# untitled.net
KiCad netlist of a schematic drawn in EAGLE
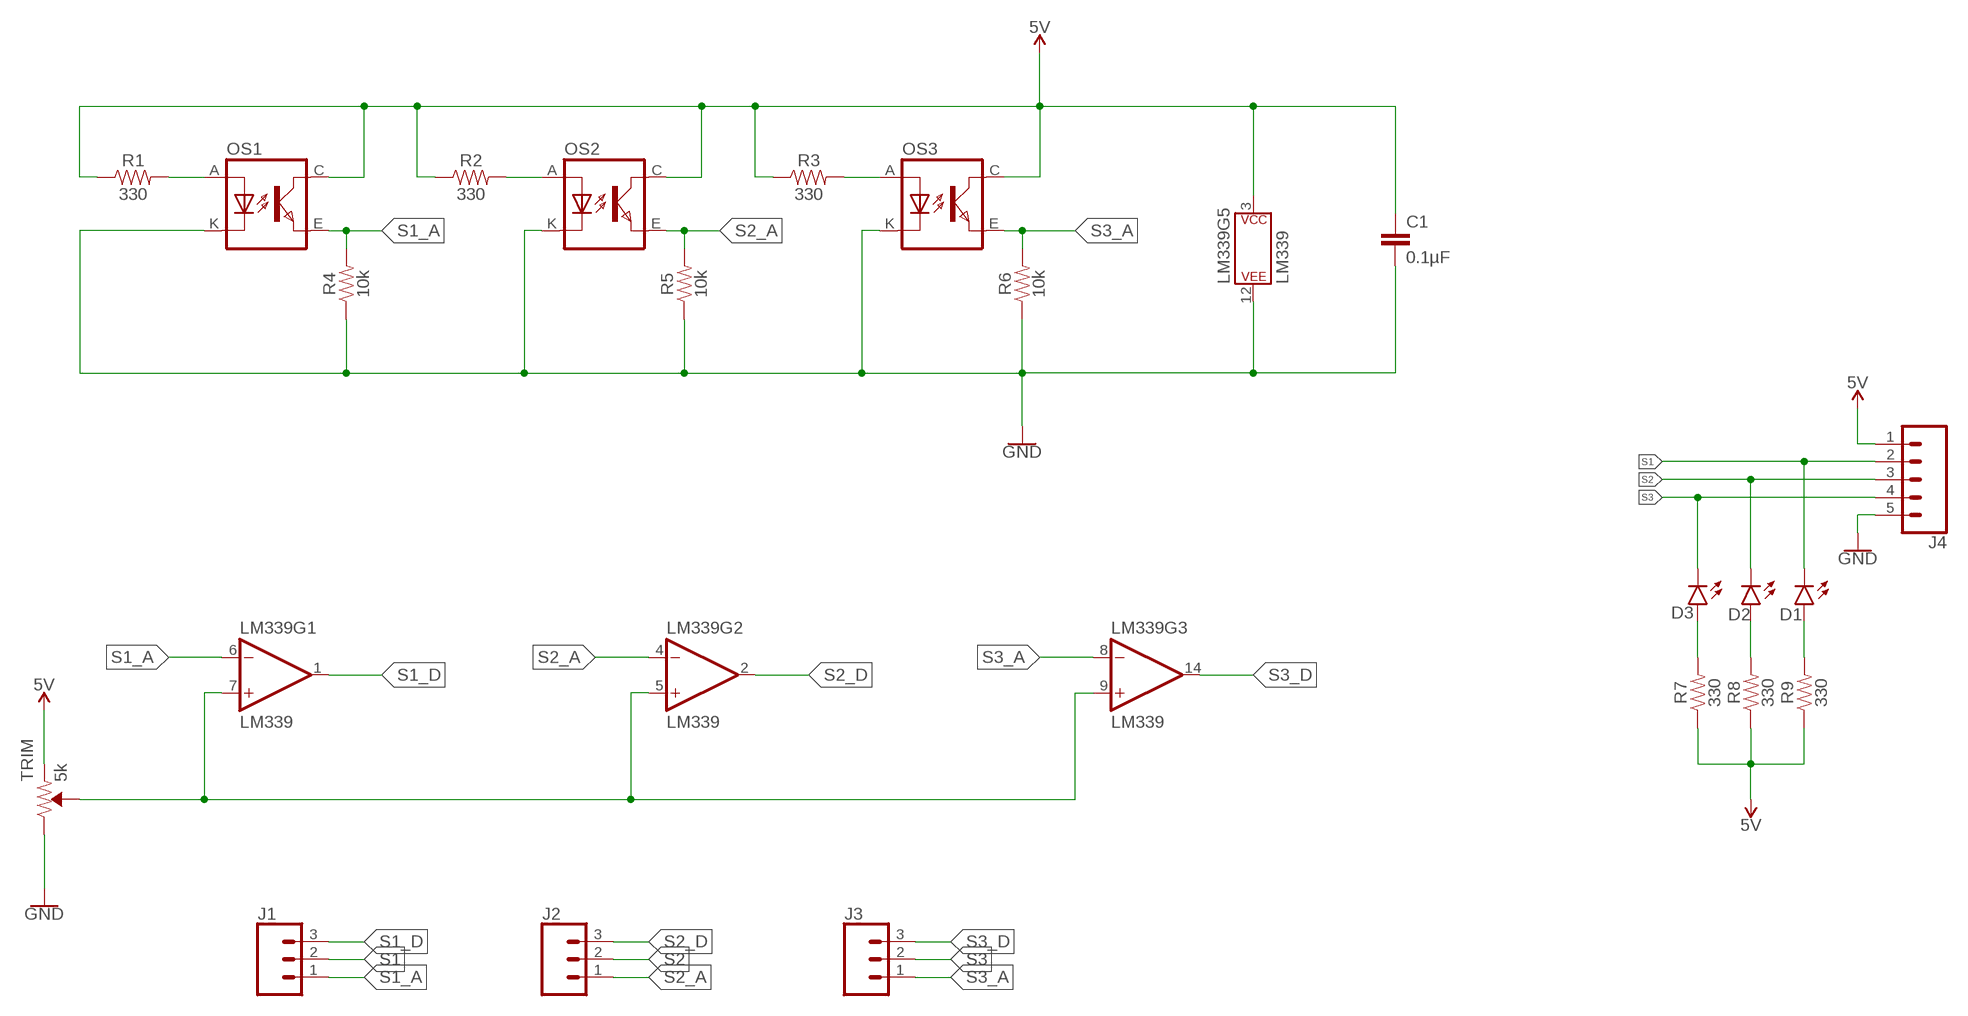
[diagram p0: schematic, sheet 1]

(export (version "E")
  (design (tool "Eeschema 10.0.6"))
  (components
    (comp (ref "C1")
      (value "0.1µF")
      (footprint "eagle-import:0805")
      (libsource (lib "eagle-import") (part "0.33UF/330NF-0805-50V-10%"))
    )
    (comp (ref "D1")
      (value "LED-RED-0805")
      (footprint "eagle-import:LED-0805")
      (libsource (lib "eagle-import") (part "LED-RED-0805"))
    )
    (comp (ref "D2")
      (value "LED-RED-0805")
      (footprint "eagle-import:LED-0805")
      (libsource (lib "eagle-import") (part "LED-RED-0805"))
    )
    (comp (ref "D3")
      (value "LED-RED-0805")
      (footprint "eagle-import:LED-0805")
      (libsource (lib "eagle-import") (part "LED-RED-0805"))
    )
    (comp (ref "J1")
      (value "CONN_03")
      (footprint "eagle-import:1X03")
      (libsource (lib "eagle-import") (part "CONN_03"))
    )
    (comp (ref "J2")
      (value "CONN_03")
      (footprint "eagle-import:1X03")
      (libsource (lib "eagle-import") (part "CONN_03"))
    )
    (comp (ref "J3")
      (value "CONN_03")
      (footprint "eagle-import:1X03")
      (libsource (lib "eagle-import") (part "CONN_03"))
    )
    (comp (ref "J4")
      (value "CONN_05PTH")
      (footprint "eagle-import:1X05")
      (libsource (lib "eagle-import") (part "CONN_05PTH"))
    )
    (comp (ref "LM339")
      (value "LM339")
      (footprint "eagle-import:TSSOP-14")
      (libsource (lib "eagle-import") (part "LM339"))
    )
    (comp (ref "OS1")
      (value "TCRT5000")
      (footprint "eagle-import:TCRT5000")
      (libsource (lib "eagle-import") (part "TCRT5000"))
    )
    (comp (ref "OS2")
      (value "TCRT5000")
      (footprint "eagle-import:TCRT5000")
      (libsource (lib "eagle-import") (part "TCRT5000"))
    )
    (comp (ref "OS3")
      (value "TCRT5000")
      (footprint "eagle-import:TCRT5000")
      (libsource (lib "eagle-import") (part "TCRT5000"))
    )
    (comp (ref "R1")
      (value "330")
      (footprint "eagle-import:0805")
      (libsource (lib "eagle-import") (part "0.3OHM-0805-1/8W-1%"))
    )
    (comp (ref "R2")
      (value "330")
      (footprint "eagle-import:0805")
      (libsource (lib "eagle-import") (part "0.3OHM-0805-1/8W-1%"))
    )
    (comp (ref "R3")
      (value "330")
      (footprint "eagle-import:0805")
      (libsource (lib "eagle-import") (part "0.3OHM-0805-1/8W-1%"))
    )
    (comp (ref "R4")
      (value "10k")
      (footprint "eagle-import:0805")
      (libsource (lib "eagle-import") (part "0.3OHM-0805-1/8W-1%"))
    )
    (comp (ref "R5")
      (value "10k")
      (footprint "eagle-import:0805")
      (libsource (lib "eagle-import") (part "0.3OHM-0805-1/8W-1%"))
    )
    (comp (ref "R6")
      (value "10k")
      (footprint "eagle-import:0805")
      (libsource (lib "eagle-import") (part "0.3OHM-0805-1/8W-1%"))
    )
    (comp (ref "R7")
      (value "330")
      (footprint "eagle-import:0805")
      (libsource (lib "eagle-import") (part "0.3OHM-0805-1/8W-1%"))
    )
    (comp (ref "R8")
      (value "330")
      (footprint "eagle-import:0805")
      (libsource (lib "eagle-import") (part "0.3OHM-0805-1/8W-1%"))
    )
    (comp (ref "R9")
      (value "330")
      (footprint "eagle-import:0805")
      (libsource (lib "eagle-import") (part "0.3OHM-0805-1/8W-1%"))
    )
    (comp (ref "TRIM")
      (value "5k")
      (footprint "eagle-import:TRIMPOT-SMD-5MM")
      (libsource (lib "eagle-import") (part "TRIMPOT-SMD-5MM-CLOSED-1/4W-20%"))
    )
  )
  (nets
    (net (code "1") (name "5V") (class "Default")
      (node (ref "C1") (pin "1") (pinfunction "1_1") (pintype "passive"))
      (node (ref "J4") (pin "1") (pinfunction "1_1") (pintype "passive"))
      (node (ref "LM339") (pin "3") (pinfunction "P$V+_3") (pintype "bidirectional"))
      (node (ref "OS1") (pin "C") (pinfunction "COLLECTOR_C") (pintype "passive"))
      (node (ref "OS2") (pin "C") (pinfunction "COLLECTOR_C") (pintype "passive"))
      (node (ref "OS3") (pin "C") (pinfunction "COLLECTOR_C") (pintype "passive"))
      (node (ref "R1") (pin "1") (pinfunction "1_1") (pintype "passive"))
      (node (ref "R2") (pin "1") (pinfunction "1_1") (pintype "passive"))
      (node (ref "R3") (pin "1") (pinfunction "1_1") (pintype "passive"))
      (node (ref "R7") (pin "1") (pinfunction "1_1") (pintype "passive"))
      (node (ref "R8") (pin "1") (pinfunction "1_1") (pintype "passive"))
      (node (ref "R9") (pin "1") (pinfunction "1_1") (pintype "passive"))
      (node (ref "TRIM") (pin "A") (pinfunction "CCW_A") (pintype "passive"))
    )
    (net (code "2") (name "GND") (class "Default")
      (node (ref "C1") (pin "2") (pinfunction "2_2") (pintype "passive"))
      (node (ref "J4") (pin "5") (pinfunction "5_5") (pintype "passive"))
      (node (ref "LM339") (pin "12") (pinfunction "P$V-_12") (pintype "bidirectional"))
      (node (ref "OS1") (pin "K") (pinfunction "CATHODE_K") (pintype "passive"))
      (node (ref "OS2") (pin "K") (pinfunction "CATHODE_K") (pintype "passive"))
      (node (ref "OS3") (pin "K") (pinfunction "CATHODE_K") (pintype "passive"))
      (node (ref "R4") (pin "1") (pinfunction "1_1") (pintype "passive"))
      (node (ref "R5") (pin "1") (pinfunction "1_1") (pintype "passive"))
      (node (ref "R6") (pin "1") (pinfunction "1_1") (pintype "passive"))
      (node (ref "TRIM") (pin "C") (pinfunction "CW_C") (pintype "passive"))
    )
    (net (code "3") (name "Net-(D1-PadA)") (class "Default")
      (node (ref "D1") (pin "A") (pinfunction "A_A") (pintype "passive"))
      (node (ref "R9") (pin "2") (pinfunction "2_2") (pintype "passive"))
    )
    (net (code "4") (name "Net-(D2-PadA)") (class "Default")
      (node (ref "D2") (pin "A") (pinfunction "A_A") (pintype "passive"))
      (node (ref "R8") (pin "2") (pinfunction "2_2") (pintype "passive"))
    )
    (net (code "5") (name "Net-(D3-PadA)") (class "Default")
      (node (ref "D3") (pin "A") (pinfunction "A_A") (pintype "passive"))
      (node (ref "R7") (pin "2") (pinfunction "2_2") (pintype "passive"))
    )
    (net (code "6") (name "Net-(LM339A-+IN)") (class "Default")
      (node (ref "LM339") (pin "5") (pinfunction "+IN_5") (pintype "input"))
      (node (ref "LM339") (pin "7") (pinfunction "+IN_7") (pintype "input"))
      (node (ref "LM339") (pin "9") (pinfunction "+IN_9") (pintype "input"))
      (node (ref "TRIM") (pin "B") (pinfunction "WIPER_B") (pintype "passive"))
    )
    (net (code "7") (name "Net-(OS1-ANODE)") (class "Default")
      (node (ref "OS1") (pin "A") (pinfunction "ANODE_A") (pintype "passive"))
      (node (ref "R1") (pin "2") (pinfunction "2_2") (pintype "passive"))
    )
    (net (code "8") (name "Net-(OS2-ANODE)") (class "Default")
      (node (ref "OS2") (pin "A") (pinfunction "ANODE_A") (pintype "passive"))
      (node (ref "R2") (pin "2") (pinfunction "2_2") (pintype "passive"))
    )
    (net (code "9") (name "Net-(OS3-ANODE)") (class "Default")
      (node (ref "OS3") (pin "A") (pinfunction "ANODE_A") (pintype "passive"))
      (node (ref "R3") (pin "2") (pinfunction "2_2") (pintype "passive"))
    )
    (net (code "10") (name "S1") (class "Default")
      (node (ref "D1") (pin "C") (pinfunction "C_C") (pintype "passive"))
      (node (ref "J1") (pin "2") (pinfunction "2_2") (pintype "passive"))
      (node (ref "J4") (pin "2") (pinfunction "2_2") (pintype "passive"))
    )
    (net (code "11") (name "S1_A") (class "Default")
      (node (ref "J1") (pin "1") (pinfunction "1_1") (pintype "passive"))
      (node (ref "LM339") (pin "6") (pinfunction "-IN_6") (pintype "input"))
      (node (ref "OS1") (pin "E") (pinfunction "EMITTER_E") (pintype "passive"))
      (node (ref "R4") (pin "2") (pinfunction "2_2") (pintype "passive"))
    )
    (net (code "12") (name "S1_D") (class "Default")
      (node (ref "J1") (pin "3") (pinfunction "3_3") (pintype "passive"))
      (node (ref "LM339") (pin "1") (pinfunction "OUT_1") (pintype "output"))
    )
    (net (code "13") (name "S2") (class "Default")
      (node (ref "D2") (pin "C") (pinfunction "C_C") (pintype "passive"))
      (node (ref "J2") (pin "2") (pinfunction "2_2") (pintype "passive"))
      (node (ref "J4") (pin "3") (pinfunction "3_3") (pintype "passive"))
    )
    (net (code "14") (name "S2_A") (class "Default")
      (node (ref "J2") (pin "1") (pinfunction "1_1") (pintype "passive"))
      (node (ref "LM339") (pin "4") (pinfunction "-IN_4") (pintype "input"))
      (node (ref "OS2") (pin "E") (pinfunction "EMITTER_E") (pintype "passive"))
      (node (ref "R5") (pin "2") (pinfunction "2_2") (pintype "passive"))
    )
    (net (code "15") (name "S2_D") (class "Default")
      (node (ref "J2") (pin "3") (pinfunction "3_3") (pintype "passive"))
      (node (ref "LM339") (pin "2") (pinfunction "OUT_2") (pintype "output"))
    )
    (net (code "16") (name "S3") (class "Default")
      (node (ref "D3") (pin "C") (pinfunction "C_C") (pintype "passive"))
      (node (ref "J3") (pin "2") (pinfunction "2_2") (pintype "passive"))
      (node (ref "J4") (pin "4") (pinfunction "4_4") (pintype "passive"))
    )
    (net (code "17") (name "S3_A") (class "Default")
      (node (ref "J3") (pin "1") (pinfunction "1_1") (pintype "passive"))
      (node (ref "LM339") (pin "8") (pinfunction "-IN_8") (pintype "input"))
      (node (ref "OS3") (pin "E") (pinfunction "EMITTER_E") (pintype "passive"))
      (node (ref "R6") (pin "2") (pinfunction "2_2") (pintype "passive"))
    )
    (net (code "18") (name "S3_D") (class "Default")
      (node (ref "J3") (pin "3") (pinfunction "3_3") (pintype "passive"))
      (node (ref "LM339") (pin "14") (pinfunction "OUT_14") (pintype "output"))
    )
  )
)
